# LPCB235_-_MLP_CHANNEL.net
KiCad netlist of a schematic drawn in Altium Designer
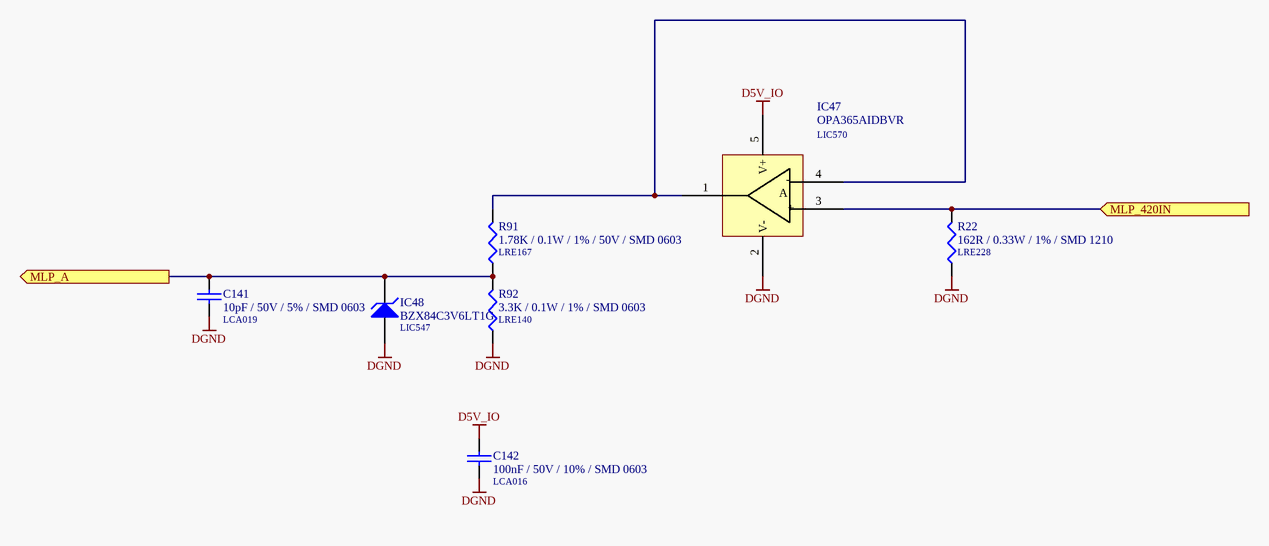
[diagram p0: LPCB235 - MLP CHANNEL.SchDoc]

(export (version "E")
  (design (tool "Eeschema 10.0.6"))
  (components
    (comp (ref "C141")
      (value "10pF / 50V / 5% / SMD 0603")
      (footprint "LFP011__CC1608-0603-IPC7351_B")
      (description "Capacitor, Ceramic Chip, 10pF, 50V, 5%, SMD 0603 [LCA019]")
      (fields (field (name "LDL_NUMBER") "LCA019"))
      (libsource (lib "LDL_Capacitors") (part "10pF / 50V / 5% / SMD 0603"))
    )
    (comp (ref "C142")
      (value "100nF / 50V / 10% / SMD 0603")
      (footprint "LFP011__CC1608-0603-IPC7351_B")
      (description "Capacitor, Ceramic Chip, 100nF (0.1uF), 50V, 5%, SMD 0603 [LCA016]")
      (fields (field (name "LDL_NUMBER") "LCA016"))
      (libsource (lib "LDL_Capacitors") (part "100nF / 50V / 10% / SMD 0603"))
    )
    (comp (ref "IC47")
      (value "OPA365AIDBVR")
      (footprint "LFP114__R-PDSO-G5")
      (description "IC, OpAmp, 1-Channel, Low Noise, SMD SOT-23-5 [LIC570]")
      (fields (field (name "LDL_NUMBER") "LIC570"))
      (libsource (lib "LDL_Semiconductors") (part "OPA365AIDBVR"))
    )
    (comp (ref "IC48")
      (value "BZX84C3V6LT1G")
      (footprint "LFP021__SOT23")
      (description "Diode, Zener, 3.6V, 0.225W, SMD [LIC083]")
      (fields (field (name "LDL_NUMBER") "LIC547"))
      (libsource (lib "LDL_Semiconductors") (part "BZX84C3V6LT1G"))
    )
    (comp (ref "R22")
      (value "162R / 0.33W / 1% / SMD 1210")
      (footprint "LFP028__CR3225-1210")
      (description "Resistor, Ceramic Chip, 162R, 0.33W, 1%, SMD 1210 [LRE228]")
      (fields (field (name "LDL_NUMBER") "LRE228"))
      (libsource (lib "LDL_Resistors") (part "162R / 0.33W / 1% / SMD 1210"))
    )
    (comp (ref "R91")
      (value "1.78K / 0.1W / 1% / 50V / SMD 0603")
      (footprint "LFP020__CR1608-0603-IPC7351_B")
      (description "Resistor, Ceramic Chip, 1.78K, 0.1W, 1%, SMD 0603 [LRE167]")
      (fields (field (name "LDL_NUMBER") "LRE167"))
      (libsource (lib "LDL_Resistors") (part "1.78K / 0.1W / 1% / 50V / SMD 0603"))
    )
    (comp (ref "R92")
      (value "3.3K / 0.1W / 1% / SMD 0603")
      (footprint "LFP020__CR1608-0603-IPC7351_B")
      (description "Resistor, Ceramic Chip, 3.3K0, 0.1W, 1%, SMD 0603 [LRE140]")
      (fields (field (name "LDL_NUMBER") "LRE140"))
      (libsource (lib "LDL_Resistors") (part "3.3K / 0.1W / 1% / SMD 0603"))
    )
  )
  (nets
    (net (code "1") (name "/MLP_420IN") (class "Default")
      (node (ref "IC47") (pin "3") (pinfunction "+IN_A_3") (pintype "passive"))
      (node (ref "R22") (pin "2") (pintype "passive"))
    )
    (net (code "2") (name "/MLP_A") (class "Default")
      (node (ref "C141") (pin "1") (pintype "passive"))
      (node (ref "IC48") (pin "3") (pinfunction "K_3") (pintype "passive"))
      (node (ref "R91") (pin "1") (pintype "passive"))
      (node (ref "R92") (pin "2") (pintype "passive"))
    )
    (net (code "3") (name "D5V_IO") (class "Default")
      (node (ref "C142") (pin "1") (pintype "passive"))
      (node (ref "IC47") (pin "5") (pinfunction "V+_5") (pintype "passive"))
    )
    (net (code "4") (name "DGND") (class "Default")
      (node (ref "C141") (pin "2") (pintype "passive"))
      (node (ref "C142") (pin "2") (pintype "passive"))
      (node (ref "IC47") (pin "2") (pinfunction "V-_2") (pintype "passive"))
      (node (ref "IC48") (pin "1") (pinfunction "A_1") (pintype "passive"))
      (node (ref "R22") (pin "1") (pintype "passive"))
      (node (ref "R92") (pin "1") (pintype "passive"))
    )
    (net (code "5") (name "Net-(IC47--IN_A)") (class "Default")
      (node (ref "IC47") (pin "1") (pinfunction "OUT_A_1") (pintype "passive"))
      (node (ref "IC47") (pin "4") (pinfunction "-IN_A_4") (pintype "passive"))
      (node (ref "R91") (pin "2") (pintype "passive"))
    )
  )
)
